# Radio_EV1.net
KiCad netlist of a schematic drawn in EAGLE
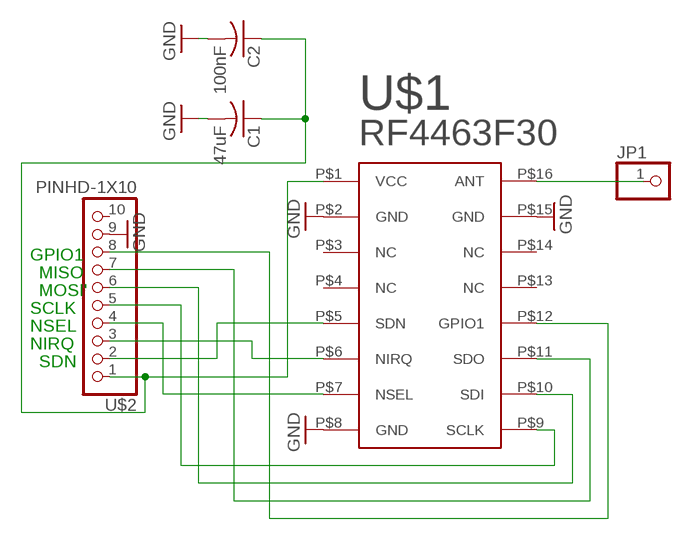
[diagram p0: schematic, sheet 1]

(export (version "E")
  (design (tool "Eeschema 10.0.6"))
  (components
    (comp (ref "C1")
      (value "47uF")
      (footprint "eagle-import:C0805")
      (libsource (lib "eagle-import") (part "C-USC0805"))
    )
    (comp (ref "C2")
      (value "100nF")
      (footprint "eagle-import:C0805")
      (libsource (lib "eagle-import") (part "C-USC0805"))
    )
    (comp (ref "JP1")
      (value "PINHD-1X1CB")
      (footprint "eagle-import:1X01-CLEANBIG")
      (libsource (lib "eagle-import") (part "PINHD-1X1CB"))
    )
    (comp (ref "U$1")
      (value "RF4463F30")
      (footprint "eagle-import:RF4463F30")
      (libsource (lib "eagle-import") (part "RF4463F30"))
    )
    (comp (ref "U$2")
      (value "PINHD-1X10")
      (footprint "eagle-import:1X10-BIG")
      (libsource (lib "eagle-import") (part "PINHD-1X10"))
    )
  )
  (nets
    (net (code "1") (name "GND") (class "Default")
      (node (ref "C1") (pin "2") (pinfunction "2_2") (pintype "passive"))
      (node (ref "C2") (pin "2") (pinfunction "2_2") (pintype "passive"))
      (node (ref "U$1") (pin "P$15") (pinfunction "GND_P$15") (pintype "power_in"))
      (node (ref "U$1") (pin "P$2") (pinfunction "GND_P$2") (pintype "power_in"))
      (node (ref "U$1") (pin "P$8") (pinfunction "GND_P$8") (pintype "power_in"))
      (node (ref "U$2") (pin "9") (pinfunction "9_9") (pintype "passive"))
    )
    (net (code "2") (name "Net-(U$1-ANT)") (class "Default")
      (node (ref "JP1") (pin "1") (pinfunction "1_1") (pintype "passive"))
      (node (ref "U$1") (pin "P$16") (pinfunction "ANT_P$16") (pintype "bidirectional"))
    )
    (net (code "3") (name "Net-(U$1-GPIO1)") (class "Default")
      (node (ref "U$1") (pin "P$12") (pinfunction "GPIO1_P$12") (pintype "bidirectional"))
      (node (ref "U$2") (pin "8") (pinfunction "8_8") (pintype "passive"))
    )
    (net (code "4") (name "Net-(U$1-NIRQ)") (class "Default")
      (node (ref "U$1") (pin "P$6") (pinfunction "NIRQ_P$6") (pintype "bidirectional"))
      (node (ref "U$2") (pin "3") (pinfunction "3_3") (pintype "passive"))
    )
    (net (code "5") (name "Net-(U$1-NSEL)") (class "Default")
      (node (ref "U$1") (pin "P$7") (pinfunction "NSEL_P$7") (pintype "bidirectional"))
      (node (ref "U$2") (pin "4") (pinfunction "4_4") (pintype "passive"))
    )
    (net (code "6") (name "Net-(U$1-SCLK)") (class "Default")
      (node (ref "U$1") (pin "P$9") (pinfunction "SCLK_P$9") (pintype "bidirectional"))
      (node (ref "U$2") (pin "5") (pinfunction "5_5") (pintype "passive"))
    )
    (net (code "7") (name "Net-(U$1-SDI)") (class "Default")
      (node (ref "U$1") (pin "P$10") (pinfunction "SDI_P$10") (pintype "bidirectional"))
      (node (ref "U$2") (pin "6") (pinfunction "6_6") (pintype "passive"))
    )
    (net (code "8") (name "Net-(U$1-SDN)") (class "Default")
      (node (ref "U$1") (pin "P$5") (pinfunction "SDN_P$5") (pintype "bidirectional"))
      (node (ref "U$2") (pin "2") (pinfunction "2_2") (pintype "passive"))
    )
    (net (code "9") (name "Net-(U$1-SDO)") (class "Default")
      (node (ref "U$1") (pin "P$11") (pinfunction "SDO_P$11") (pintype "bidirectional"))
      (node (ref "U$2") (pin "7") (pinfunction "7_7") (pintype "passive"))
    )
    (net (code "10") (name "Net-(U$1-VCC)") (class "Default")
      (node (ref "C1") (pin "1") (pinfunction "1_1") (pintype "passive"))
      (node (ref "C2") (pin "1") (pinfunction "1_1") (pintype "passive"))
      (node (ref "U$1") (pin "P$1") (pinfunction "VCC_P$1") (pintype "power_in"))
      (node (ref "U$2") (pin "1") (pinfunction "1_1") (pintype "passive"))
    )
    (net (code "11") (name "unconnected-(U$1-NC-PadP$3)") (class "Default")
      (node (ref "U$1") (pin "P$3") (pinfunction "NC_P$3") (pintype "no_connect"))
    )
    (net (code "12") (name "unconnected-(U$1-NC-PadP$4)") (class "Default")
      (node (ref "U$1") (pin "P$4") (pinfunction "NC_P$4") (pintype "no_connect"))
    )
    (net (code "13") (name "unconnected-(U$1-NC-PadP$13)") (class "Default")
      (node (ref "U$1") (pin "P$13") (pinfunction "NC_P$13") (pintype "no_connect"))
    )
    (net (code "14") (name "unconnected-(U$1-NC-PadP$14)") (class "Default")
      (node (ref "U$1") (pin "P$14") (pinfunction "NC_P$14") (pintype "no_connect"))
    )
    (net (code "15") (name "unconnected-(U$2-Pad10)") (class "Default")
      (node (ref "U$2") (pin "10") (pinfunction "10_10") (pintype "passive"))
    )
  )
)
